# design.net
KiCad netlist of a schematic drawn in Altium Designer
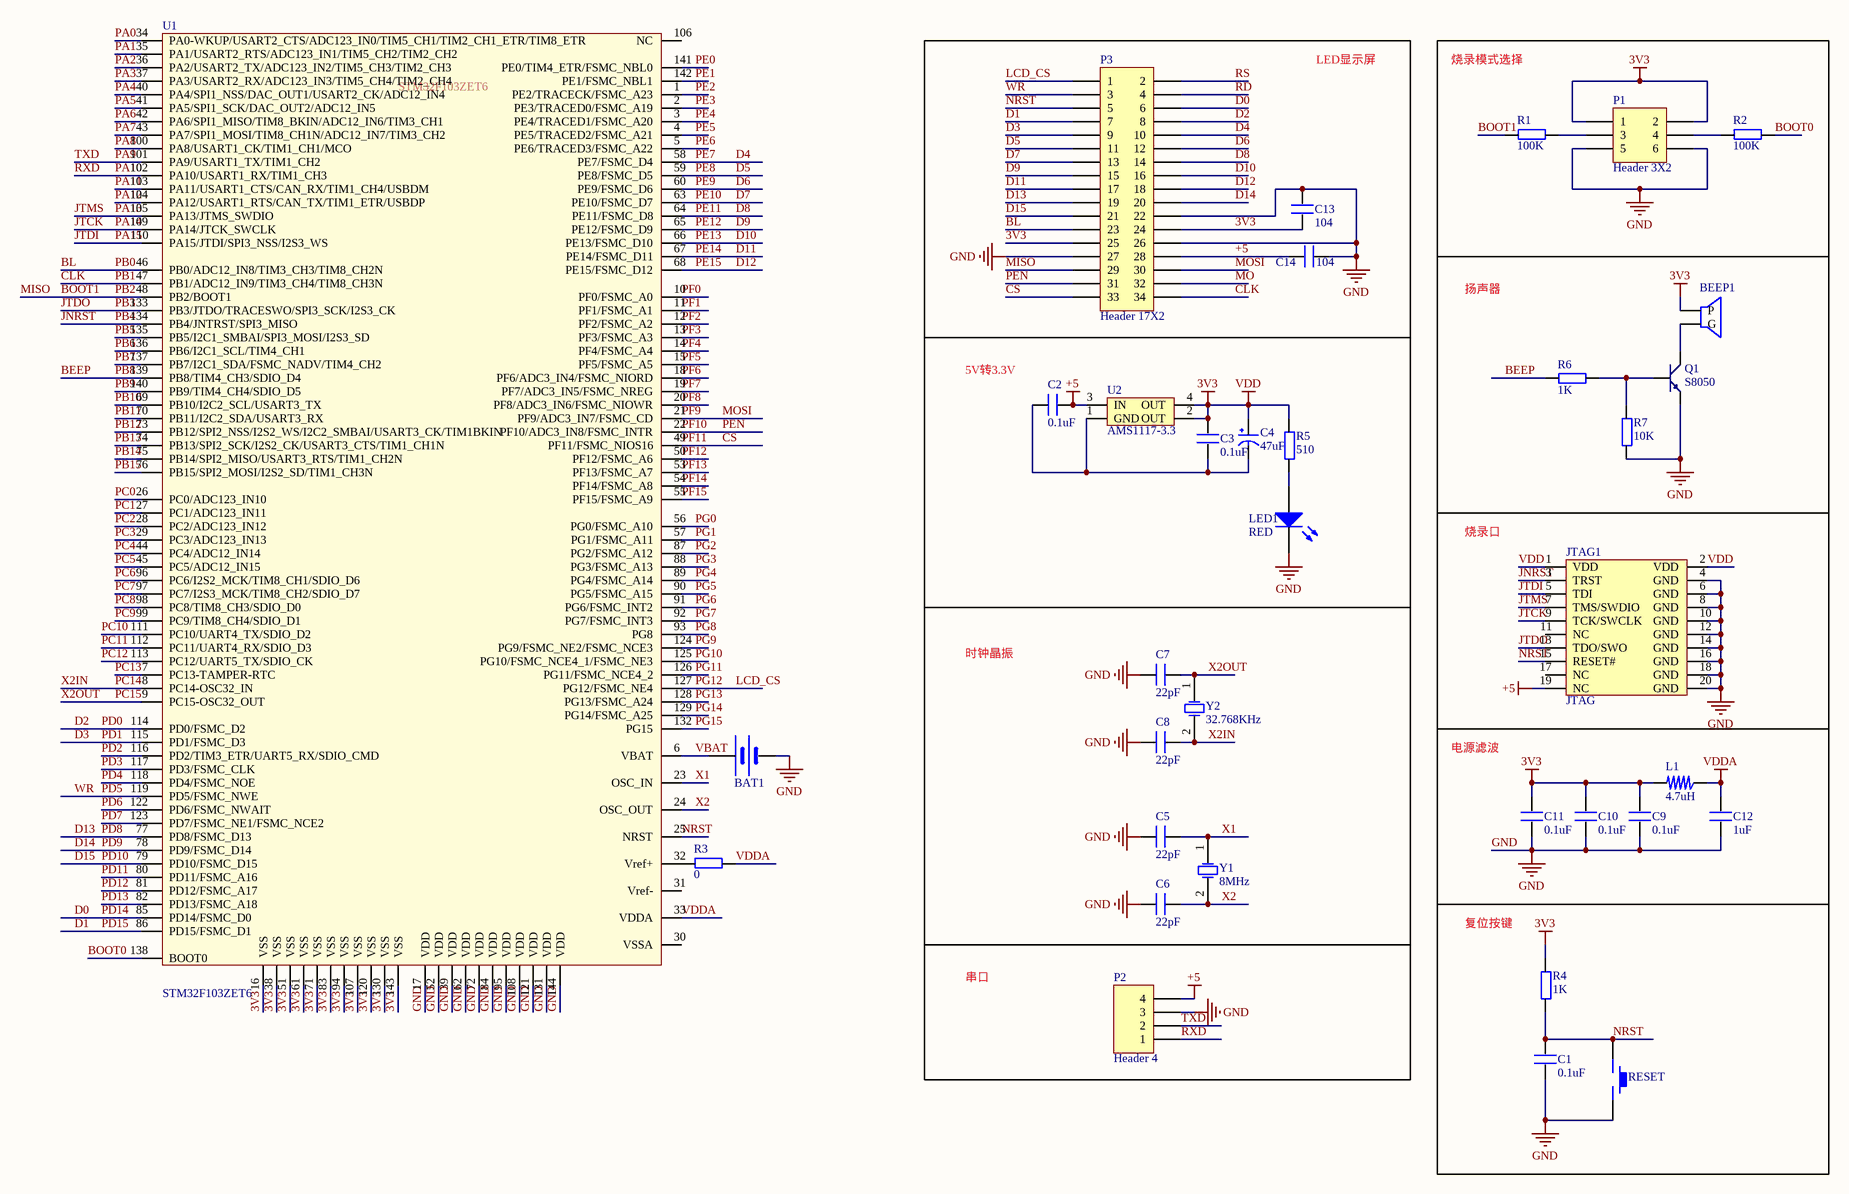
[diagram p0: 新苗.SchDoc]

(export (version "E")
  (design (tool "Eeschema 10.0.6"))
  (components
    (comp (ref "BAT1")
      (value "BATT")
      (footprint "BATM")
      (libsource (lib "WarShip V3 STM32103封装库") (part "BAT"))
    )
    (comp (ref "BEEP1")
      (value "BEEP")
      (footprint "BELL-5")
      (libsource (lib "WarShip V3 STM32103封装库") (part "BEEP"))
    )
    (comp (ref "C1")
      (value "0.1uF")
      (footprint "0603P")
      (libsource (lib "WarShip V3 STM32103封装库") (part "C"))
    )
    (comp (ref "C2")
      (value "0.1uF")
      (footprint "0603P")
      (libsource (lib "WarShip V3 STM32103封装库") (part "C"))
    )
    (comp (ref "C3")
      (value "0.1uF")
      (footprint "0603P")
      (libsource (lib "WarShip V3 STM32103封装库") (part "C"))
    )
    (comp (ref "C4")
      (value "47uF")
      (footprint "CC6.56.5")
      (libsource (lib "WarShip V3 STM32103封装库") (part "CAP"))
    )
    (comp (ref "C5") (value "22pF") (footprint "0603P") (libsource (lib "WarShip V3 STM32103封装库") (part "C")))
    (comp (ref "C6") (value "22pF") (footprint "0603P") (libsource (lib "WarShip V3 STM32103封装库") (part "C")))
    (comp (ref "C7") (value "22pF") (footprint "0603P") (libsource (lib "WarShip V3 STM32103封装库") (part "C")))
    (comp (ref "C8") (value "22pF") (footprint "0603P") (libsource (lib "WarShip V3 STM32103封装库") (part "C")))
    (comp (ref "C9")
      (value "0.1uF")
      (footprint "0603P")
      (libsource (lib "WarShip V3 STM32103封装库") (part "C"))
    )
    (comp (ref "C10")
      (value "0.1uF")
      (footprint "0603P")
      (libsource (lib "WarShip V3 STM32103封装库") (part "C"))
    )
    (comp (ref "C11")
      (value "0.1uF")
      (footprint "0603P")
      (libsource (lib "WarShip V3 STM32103封装库") (part "C"))
    )
    (comp (ref "C12") (value "1uF") (footprint "0603P") (libsource (lib "WarShip V3 STM32103封装库") (part "C")))
    (comp (ref "C13") (value "104") (footprint "0603P") (libsource (lib "WarShip V3 STM32103封装库") (part "C")))
    (comp (ref "C14") (value "104") (footprint "0603P") (libsource (lib "WarShip V3 STM32103封装库") (part "C")))
    (comp (ref "JTAG1")
      (value "JTAG")
      (footprint "JTAG_20")
      (libsource (lib "WarShip V3 STM32103封装库") (part "JTAG"))
    )
    (comp (ref "L1")
      (value "4.7uH")
      (footprint "L_SOP74")
      (libsource (lib "WarShip V3 STM32103封装库") (part "L_SOP"))
    )
    (comp (ref "LED1")
      (value "RED")
      (footprint "SMDLED")
      (description "Typical RED, GREEN, YELLOW, AMBER GaAs LED")
      (fields (field (name "PUBLISHER") "Altium Limited"))
      (libsource (lib "WarShip V3 STM32103封装库") (part "LED2"))
    )
    (comp (ref "P1")
      (value "Header 3X2")
      (footprint "HDR2X3")
      (description "Header, 3-Pin, Dual row")
      (fields (field (name "PUBLISHER") "Altium Limited"))
      (libsource (lib "Miscellaneous Connectors") (part "Header 3X2"))
    )
    (comp (ref "P2")
      (value "Header 4")
      (footprint "HDR1X4")
      (description "Header, 4-Pin")
      (fields (field (name "PUBLISHER") "Altium Limited"))
      (libsource (lib "WarShip V3 STM32103封装库") (part "Header 4"))
    )
    (comp (ref "P3")
      (value "Header 17X2")
      (footprint "HDR2X17")
      (description "Header, 17-Pin, Dual row")
      (fields (field (name "PUBLISHER") "Altium Limited"))
      (libsource (lib "Miscellaneous Connectors") (part "Header 17X2"))
    )
    (comp (ref "Q1")
      (value "S8050")
      (footprint "SOT-23R")
      (description "8050/BCW846/BCW847")
      (libsource (lib "WarShip V3 STM32103封装库") (part "NPN"))
    )
    (comp (ref "R1") (value "100K") (footprint "0603P") (libsource (lib "WarShip V3 STM32103封装库") (part "R")))
    (comp (ref "R2") (value "100K") (footprint "0603P") (libsource (lib "WarShip V3 STM32103封装库") (part "R")))
    (comp (ref "R3") (value "0") (footprint "0603P") (libsource (lib "WarShip V3 STM32103封装库") (part "R")))
    (comp (ref "R4") (value "1K") (footprint "0603P") (libsource (lib "WarShip V3 STM32103封装库") (part "R")))
    (comp (ref "R5") (value "510") (footprint "0603P") (libsource (lib "WarShip V3 STM32103封装库") (part "R")))
    (comp (ref "R6") (value "1K") (footprint "0603P") (libsource (lib "WarShip V3 STM32103封装库") (part "R")))
    (comp (ref "R7") (value "10K") (footprint "0603P") (libsource (lib "WarShip V3 STM32103封装库") (part "R")))
    (comp (ref "RESET")
      (value "KEY_M")
      (footprint "KEY_M")
      (libsource (lib "WarShip V3 STM32103封装库") (part "KEY_M"))
    )
    (comp (ref "U1")
      (value "STM32F103ZET6")
      (footprint "LQFP144")
      (libsource (lib "WarShip V3 STM32103封装库") (part "STM32F103ZET6"))
    )
    (comp (ref "U2")
      (value "AMS1117-3.3")
      (footprint "AMS1117")
      (libsource (lib "WarShip V3 STM32103封装库") (part "AMS1117"))
    )
    (comp (ref "Y1")
      (value "8MHz")
      (footprint "XTAL_US")
      (description "Crystal Oscillator")
      (fields (field (name "PUBLISHER") "Altium Limited"))
      (libsource (lib "WarShip V3 STM32103封装库") (part "XTAL"))
    )
    (comp (ref "Y2")
      (value "32.768KHz")
      (footprint "XTAL_US")
      (description "Crystal Oscillator")
      (fields (field (name "PUBLISHER") "Altium Limited"))
      (libsource (lib "WarShip V3 STM32103封装库") (part "XTAL"))
    )
  )
  (nets
    (net (code "1") (name "+5") (class "Default")
      (node (ref "C14") (pin "2") (pintype "passive"))
      (node (ref "C2") (pin "1") (pintype "passive"))
      (node (ref "JTAG1") (pin "19") (pinfunction "NC_19") (pintype "passive"))
      (node (ref "P2") (pin "4") (pinfunction "4_4") (pintype "passive"))
      (node (ref "P3") (pin "28") (pinfunction "28_28") (pintype "passive"))
      (node (ref "U2") (pin "3") (pinfunction "IN_3") (pintype "passive"))
    )
    (net (code "2") (name "/BEEP") (class "Default")
      (node (ref "R6") (pin "1") (pintype "passive"))
      (node (ref "U1") (pin "139") (pinfunction "PB8/TIM4_CH3/SDIO_D4_139") (pintype "passive"))
    )
    (net (code "3") (name "/BL") (class "Default")
      (node (ref "P3") (pin "23") (pinfunction "23_23") (pintype "passive"))
      (node (ref "U1") (pin "46") (pinfunction "PB0/ADC12_IN8/TIM3_CH3/TIM8_CH2N_46") (pintype "passive"))
    )
    (net (code "4") (name "/BOOT0") (class "Default")
      (node (ref "R2") (pin "1") (pintype "passive"))
      (node (ref "U1") (pin "138") (pinfunction "BOOT0_138") (pintype "passive"))
    )
    (net (code "5") (name "/BOOT1") (class "Default")
      (node (ref "P3") (pin "29") (pinfunction "29_29") (pintype "passive"))
      (node (ref "R1") (pin "2") (pintype "passive"))
      (node (ref "U1") (pin "48") (pinfunction "PB2/BOOT1_48") (pintype "passive"))
    )
    (net (code "6") (name "/CLK") (class "Default")
      (node (ref "P3") (pin "34") (pinfunction "34_34") (pintype "passive"))
      (node (ref "U1") (pin "47") (pinfunction "PB1/ADC12_IN9/TIM3_CH4/TIM8_CH3N_47") (pintype "passive"))
    )
    (net (code "7") (name "/CS") (class "Default")
      (node (ref "P3") (pin "33") (pinfunction "33_33") (pintype "passive"))
      (node (ref "U1") (pin "49") (pinfunction "PF11/FSMC_NIOS16_49") (pintype "passive"))
    )
    (net (code "8") (name "/D0") (class "Default")
      (node (ref "P3") (pin "6") (pinfunction "6_6") (pintype "passive"))
      (node (ref "U1") (pin "85") (pinfunction "PD14/FSMC_D0_85") (pintype "passive"))
    )
    (net (code "9") (name "/D1") (class "Default")
      (node (ref "P3") (pin "7") (pinfunction "7_7") (pintype "passive"))
      (node (ref "U1") (pin "86") (pinfunction "PD15/FSMC_D1_86") (pintype "passive"))
    )
    (net (code "10") (name "/D2") (class "Default")
      (node (ref "P3") (pin "8") (pinfunction "8_8") (pintype "passive"))
      (node (ref "U1") (pin "114") (pinfunction "PD0/FSMC_D2_114") (pintype "passive"))
    )
    (net (code "11") (name "/D3") (class "Default")
      (node (ref "P3") (pin "9") (pinfunction "9_9") (pintype "passive"))
      (node (ref "U1") (pin "115") (pinfunction "PD1/FSMC_D3_115") (pintype "passive"))
    )
    (net (code "12") (name "/D4") (class "Default")
      (node (ref "P3") (pin "10") (pinfunction "10_10") (pintype "passive"))
      (node (ref "U1") (pin "58") (pinfunction "PE7/FSMC_D4_58") (pintype "passive"))
    )
    (net (code "13") (name "/D5") (class "Default")
      (node (ref "P3") (pin "11") (pinfunction "11_11") (pintype "passive"))
      (node (ref "U1") (pin "59") (pinfunction "PE8/FSMC_D5_59") (pintype "passive"))
    )
    (net (code "14") (name "/D6") (class "Default")
      (node (ref "P3") (pin "12") (pinfunction "12_12") (pintype "passive"))
      (node (ref "U1") (pin "60") (pinfunction "PE9/FSMC_D6_60") (pintype "passive"))
    )
    (net (code "15") (name "/D7") (class "Default")
      (node (ref "P3") (pin "13") (pinfunction "13_13") (pintype "passive"))
      (node (ref "U1") (pin "63") (pinfunction "PE10/FSMC_D7_63") (pintype "passive"))
    )
    (net (code "16") (name "/D8") (class "Default")
      (node (ref "P3") (pin "14") (pinfunction "14_14") (pintype "passive"))
      (node (ref "U1") (pin "64") (pinfunction "PE11/FSMC_D8_64") (pintype "passive"))
    )
    (net (code "17") (name "/D9") (class "Default")
      (node (ref "P3") (pin "15") (pinfunction "15_15") (pintype "passive"))
      (node (ref "U1") (pin "65") (pinfunction "PE12/FSMC_D9_65") (pintype "passive"))
    )
    (net (code "18") (name "/D10") (class "Default")
      (node (ref "P3") (pin "16") (pinfunction "16_16") (pintype "passive"))
      (node (ref "U1") (pin "66") (pinfunction "PE13/FSMC_D10_66") (pintype "passive"))
    )
    (net (code "19") (name "/D11") (class "Default")
      (node (ref "P3") (pin "17") (pinfunction "17_17") (pintype "passive"))
      (node (ref "U1") (pin "67") (pinfunction "PE14/FSMC_D11_67") (pintype "passive"))
    )
    (net (code "20") (name "/D12") (class "Default")
      (node (ref "P3") (pin "18") (pinfunction "18_18") (pintype "passive"))
      (node (ref "U1") (pin "68") (pinfunction "PE15/FSMC_D12_68") (pintype "passive"))
    )
    (net (code "21") (name "/D13") (class "Default")
      (node (ref "P3") (pin "19") (pinfunction "19_19") (pintype "passive"))
      (node (ref "U1") (pin "77") (pinfunction "PD8/FSMC_D13_77") (pintype "passive"))
    )
    (net (code "22") (name "/D14") (class "Default")
      (node (ref "P3") (pin "20") (pinfunction "20_20") (pintype "passive"))
      (node (ref "U1") (pin "78") (pinfunction "PD9/FSMC_D14_78") (pintype "passive"))
    )
    (net (code "23") (name "/D15") (class "Default")
      (node (ref "P3") (pin "21") (pinfunction "21_21") (pintype "passive"))
      (node (ref "U1") (pin "79") (pinfunction "PD10/FSMC_D15_79") (pintype "passive"))
    )
    (net (code "24") (name "/JNRST") (class "Default")
      (node (ref "JTAG1") (pin "3") (pinfunction "TRST_3") (pintype "passive"))
      (node (ref "U1") (pin "134") (pinfunction "PB4/JNTRST/SPI3_MISO_134") (pintype "passive"))
    )
    (net (code "25") (name "/JTCK") (class "Default")
      (node (ref "JTAG1") (pin "9") (pinfunction "TCK/SWCLK_9") (pintype "passive"))
      (node (ref "U1") (pin "109") (pinfunction "PA14/JTCK_SWCLK_109") (pintype "passive"))
    )
    (net (code "26") (name "/JTDI") (class "Default")
      (node (ref "JTAG1") (pin "5") (pinfunction "TDI_5") (pintype "passive"))
      (node (ref "U1") (pin "110") (pinfunction "PA15/JTDI/SPI3_NSS/I2S3_WS_110") (pintype "passive"))
    )
    (net (code "27") (name "/JTDO") (class "Default")
      (node (ref "JTAG1") (pin "13") (pinfunction "TDO/SWO_13") (pintype "passive"))
      (node (ref "U1") (pin "133") (pinfunction "PB3/JTDO/TRACESWO/SPI3_SCK/I2S3_CK_133") (pintype "passive"))
    )
    (net (code "28") (name "/JTMS") (class "Default")
      (node (ref "JTAG1") (pin "7") (pinfunction "TMS/SWDIO_7") (pintype "passive"))
      (node (ref "U1") (pin "105") (pinfunction "PA13/JTMS_SWDIO_105") (pintype "passive"))
    )
    (net (code "29") (name "/LCD_CS") (class "Default")
      (node (ref "P3") (pin "1") (pinfunction "1_1") (pintype "passive"))
      (node (ref "U1") (pin "127") (pinfunction "PG12/FSMC_NE4_127") (pintype "passive"))
    )
    (net (code "30") (name "/MO") (class "Default")
      (node (ref "P3") (pin "32") (pinfunction "32_32") (pintype "passive"))
    )
    (net (code "31") (name "/MOSI") (class "Default")
      (node (ref "P3") (pin "30") (pinfunction "30_30") (pintype "passive"))
      (node (ref "U1") (pin "21") (pinfunction "PF9/ADC3_IN7/FSMC_CD_21") (pintype "passive"))
    )
    (net (code "32") (name "/NRST") (class "Default")
      (node (ref "C1") (pin "2") (pintype "passive"))
      (node (ref "JTAG1") (pin "15") (pinfunction "RESET#_15") (pintype "passive"))
      (node (ref "P3") (pin "5") (pinfunction "5_5") (pintype "passive"))
      (node (ref "R4") (pin "1") (pintype "passive"))
      (node (ref "RESET") (pin "1") (pinfunction "1_1") (pintype "passive"))
      (node (ref "U1") (pin "25") (pinfunction "NRST_25") (pintype "passive"))
    )
    (net (code "33") (name "/PA0") (class "Default")
      (node (ref "U1") (pin "34") (pinfunction "PA0-WKUP/USART2_CTS/ADC123_IN0/TIM5_CH1/TIM2_CH1_ETR/TIM8_ETR_34") (pintype "passive"))
    )
    (net (code "34") (name "/PA1") (class "Default")
      (node (ref "U1") (pin "35") (pinfunction "PA1/USART2_RTS/ADC123_IN1/TIM5_CH2/TIM2_CH2_35") (pintype "passive"))
    )
    (net (code "35") (name "/PA2") (class "Default")
      (node (ref "U1") (pin "36") (pinfunction "PA2/USART2_TX/ADC123_IN2/TIM5_CH3/TIM2_CH3_36") (pintype "passive"))
    )
    (net (code "36") (name "/PA3") (class "Default")
      (node (ref "U1") (pin "37") (pinfunction "PA3/USART2_RX/ADC123_IN3/TIM5_CH4/TIM2_CH4_37") (pintype "passive"))
    )
    (net (code "37") (name "/PA4") (class "Default")
      (node (ref "U1") (pin "40") (pinfunction "PA4/SPI1_NSS/DAC_OUT1/USART2_CK/ADC12_IN4_40") (pintype "passive"))
    )
    (net (code "38") (name "/PA5") (class "Default")
      (node (ref "U1") (pin "41") (pinfunction "PA5/SPI1_SCK/DAC_OUT2/ADC12_IN5_41") (pintype "passive"))
    )
    (net (code "39") (name "/PA6") (class "Default")
      (node (ref "U1") (pin "42") (pinfunction "PA6/SPI1_MISO/TIM8_BKIN/ADC12_IN6/TIM3_CH1_42") (pintype "passive"))
    )
    (net (code "40") (name "/PA7") (class "Default")
      (node (ref "U1") (pin "43") (pinfunction "PA7/SPI1_MOSI/TIM8_CH1N/ADC12_IN7/TIM3_CH2_43") (pintype "passive"))
    )
    (net (code "41") (name "/PA8") (class "Default")
      (node (ref "U1") (pin "100") (pinfunction "PA8/USART1_CK/TIM1_CH1/MCO_100") (pintype "passive"))
    )
    (net (code "42") (name "/PA9") (class "Default")
      (node (ref "P2") (pin "2") (pinfunction "2_2") (pintype "passive"))
      (node (ref "U1") (pin "101") (pinfunction "PA9/USART1_TX/TIM1_CH2_101") (pintype "passive"))
    )
    (net (code "43") (name "/PA10") (class "Default")
      (node (ref "P2") (pin "1") (pinfunction "1_1") (pintype "passive"))
      (node (ref "U1") (pin "102") (pinfunction "PA10/USART1_RX/TIM1_CH3_102") (pintype "passive"))
    )
    (net (code "44") (name "/PA11") (class "Default")
      (node (ref "U1") (pin "103") (pinfunction "PA11/USART1_CTS/CAN_RX/TIM1_CH4/USBDM_103") (pintype "passive"))
    )
    (net (code "45") (name "/PA12") (class "Default")
      (node (ref "U1") (pin "104") (pinfunction "PA12/USART1_RTS/CAN_TX/TIM1_ETR/USBDP_104") (pintype "passive"))
    )
    (net (code "46") (name "/PB5") (class "Default")
      (node (ref "U1") (pin "135") (pinfunction "PB5/I2C1_SMBAI/SPI3_MOSI/I2S3_SD_135") (pintype "passive"))
    )
    (net (code "47") (name "/PB6") (class "Default")
      (node (ref "U1") (pin "136") (pinfunction "PB6/I2C1_SCL/TIM4_CH1_136") (pintype "passive"))
    )
    (net (code "48") (name "/PB7") (class "Default")
      (node (ref "U1") (pin "137") (pinfunction "PB7/I2C1_SDA/FSMC_NADV/TIM4_CH2_137") (pintype "passive"))
    )
    (net (code "49") (name "/PB9") (class "Default")
      (node (ref "U1") (pin "140") (pinfunction "PB9/TIM4_CH4/SDIO_D5_140") (pintype "passive"))
    )
    (net (code "50") (name "/PB10") (class "Default")
      (node (ref "U1") (pin "69") (pinfunction "PB10/I2C2_SCL/USART3_TX_69") (pintype "passive"))
    )
    (net (code "51") (name "/PB11") (class "Default")
      (node (ref "U1") (pin "70") (pinfunction "PB11/I2C2_SDA/USART3_RX_70") (pintype "passive"))
    )
    (net (code "52") (name "/PB12") (class "Default")
      (node (ref "U1") (pin "73") (pinfunction "PB12/SPI2_NSS/I2S2_WS/I2C2_SMBAI/USART3_CK/TIM1BKIN_73") (pintype "passive"))
    )
    (net (code "53") (name "/PB13") (class "Default")
      (node (ref "U1") (pin "74") (pinfunction "PB13/SPI2_SCK/I2S2_CK/USART3_CTS/TIM1_CH1N_74") (pintype "passive"))
    )
    (net (code "54") (name "/PB14") (class "Default")
      (node (ref "U1") (pin "75") (pinfunction "PB14/SPI2_MISO/USART3_RTS/TIM1_CH2N_75") (pintype "passive"))
    )
    (net (code "55") (name "/PB15") (class "Default")
      (node (ref "U1") (pin "76") (pinfunction "PB15/SPI2_MOSI/I2S2_SD/TIM1_CH3N_76") (pintype "passive"))
    )
    (net (code "56") (name "/PC0") (class "Default")
      (node (ref "U1") (pin "26") (pinfunction "PC0/ADC123_IN10_26") (pintype "passive"))
    )
    (net (code "57") (name "/PC1") (class "Default")
      (node (ref "U1") (pin "27") (pinfunction "PC1/ADC123_IN11_27") (pintype "passive"))
    )
    (net (code "58") (name "/PC2") (class "Default")
      (node (ref "U1") (pin "28") (pinfunction "PC2/ADC123_IN12_28") (pintype "passive"))
    )
    (net (code "59") (name "/PC3") (class "Default")
      (node (ref "U1") (pin "29") (pinfunction "PC3/ADC123_IN13_29") (pintype "passive"))
    )
    (net (code "60") (name "/PC4") (class "Default")
      (node (ref "U1") (pin "44") (pinfunction "PC4/ADC12_IN14_44") (pintype "passive"))
    )
    (net (code "61") (name "/PC5") (class "Default")
      (node (ref "U1") (pin "45") (pinfunction "PC5/ADC12_IN15_45") (pintype "passive"))
    )
    (net (code "62") (name "/PC6") (class "Default")
      (node (ref "U1") (pin "96") (pinfunction "PC6/I2S2_MCK/TIM8_CH1/SDIO_D6_96") (pintype "passive"))
    )
    (net (code "63") (name "/PC7") (class "Default")
      (node (ref "U1") (pin "97") (pinfunction "PC7/I2S3_MCK/TIM8_CH2/SDIO_D7_97") (pintype "passive"))
    )
    (net (code "64") (name "/PC8") (class "Default")
      (node (ref "U1") (pin "98") (pinfunction "PC8/TIM8_CH3/SDIO_D0_98") (pintype "passive"))
    )
    (net (code "65") (name "/PC9") (class "Default")
      (node (ref "U1") (pin "99") (pinfunction "PC9/TIM8_CH4/SDIO_D1_99") (pintype "passive"))
    )
    (net (code "66") (name "/PC10") (class "Default")
      (node (ref "U1") (pin "111") (pinfunction "PC10/UART4_TX/SDIO_D2_111") (pintype "passive"))
    )
    (net (code "67") (name "/PC11") (class "Default")
      (node (ref "U1") (pin "112") (pinfunction "PC11/UART4_RX/SDIO_D3_112") (pintype "passive"))
    )
    (net (code "68") (name "/PC12") (class "Default")
      (node (ref "U1") (pin "113") (pinfunction "PC12/UART5_TX/SDIO_CK_113") (pintype "passive"))
    )
    (net (code "69") (name "/PC13") (class "Default")
      (node (ref "U1") (pin "7") (pinfunction "PC13-TAMPER-RTC_7") (pintype "passive"))
    )
    (net (code "70") (name "/PC14") (class "Default")
      (node (ref "C8") (pin "2") (pintype "passive"))
      (node (ref "U1") (pin "8") (pinfunction "PC14-OSC32_IN_8") (pintype "passive"))
      (node (ref "Y2") (pin "2") (pinfunction "OSC2_2") (pintype "passive"))
    )
    (net (code "71") (name "/PC15") (class "Default")
      (node (ref "C7") (pin "2") (pintype "passive"))
      (node (ref "U1") (pin "9") (pinfunction "PC15-OSC32_OUT_9") (pintype "passive"))
      (node (ref "Y2") (pin "1") (pinfunction "OSC1_1") (pintype "passive"))
    )
    (net (code "72") (name "/PD2") (class "Default")
      (node (ref "U1") (pin "116") (pinfunction "PD2/TIM3_ETR/UART5_RX/SDIO_CMD_116") (pintype "passive"))
    )
    (net (code "73") (name "/PD3") (class "Default")
      (node (ref "U1") (pin "117") (pinfunction "PD3/FSMC_CLK_117") (pintype "passive"))
    )
    (net (code "74") (name "/PD4") (class "Default")
      (node (ref "U1") (pin "118") (pinfunction "PD4/FSMC_NOE_118") (pintype "passive"))
    )
    (net (code "75") (name "/PD5") (class "Default")
      (node (ref "P3") (pin "3") (pinfunction "3_3") (pintype "passive"))
      (node (ref "U1") (pin "119") (pinfunction "PD5/FSMC_NWE_119") (pintype "passive"))
    )
    (net (code "76") (name "/PD6") (class "Default")
      (node (ref "U1") (pin "122") (pinfunction "PD6/FSMC_NWAIT_122") (pintype "passive"))
    )
    (net (code "77") (name "/PD7") (class "Default")
      (node (ref "U1") (pin "123") (pinfunction "PD7/FSMC_NE1/FSMC_NCE2_123") (pintype "passive"))
    )
    (net (code "78") (name "/PD11") (class "Default")
      (node (ref "U1") (pin "80") (pinfunction "PD11/FSMC_A16_80") (pintype "passive"))
    )
    (net (code "79") (name "/PD12") (class "Default")
      (node (ref "U1") (pin "81") (pinfunction "PD12/FSMC_A17_81") (pintype "passive"))
    )
    (net (code "80") (name "/PD13") (class "Default")
      (node (ref "U1") (pin "82") (pinfunction "PD13/FSMC_A18_82") (pintype "passive"))
    )
    (net (code "81") (name "/PE0") (class "Default")
      (node (ref "U1") (pin "141") (pinfunction "PE0/TIM4_ETR/FSMC_NBL0_141") (pintype "passive"))
    )
    (net (code "82") (name "/PE1") (class "Default")
      (node (ref "U1") (pin "142") (pinfunction "PE1/FSMC_NBL1_142") (pintype "passive"))
    )
    (net (code "83") (name "/PE2") (class "Default")
      (node (ref "U1") (pin "1") (pinfunction "PE2/TRACECK/FSMC_A23_1") (pintype "passive"))
    )
    (net (code "84") (name "/PE3") (class "Default")
      (node (ref "U1") (pin "2") (pinfunction "PE3/TRACED0/FSMC_A19_2") (pintype "passive"))
    )
    (net (code "85") (name "/PE4") (class "Default")
      (node (ref "U1") (pin "3") (pinfunction "PE4/TRACED1/FSMC_A20_3") (pintype "passive"))
    )
    (net (code "86") (name "/PE5") (class "Default")
      (node (ref "U1") (pin "4") (pinfunction "PE5/TRACED2/FSMC_A21_4") (pintype "passive"))
    )
    (net (code "87") (name "/PE6") (class "Default")
      (node (ref "U1") (pin "5") (pinfunction "PE6/TRACED3/FSMC_A22_5") (pintype "passive"))
    )
    (net (code "88") (name "/PEN") (class "Default")
      (node (ref "P3") (pin "31") (pinfunction "31_31") (pintype "passive"))
      (node (ref "U1") (pin "22") (pinfunction "PF10/ADC3_IN8/FSMC_INTR_22") (pintype "passive"))
    )
    (net (code "89") (name "/PF0") (class "Default")
      (node (ref "U1") (pin "10") (pinfunction "PF0/FSMC_A0_10") (pintype "passive"))
    )
    (net (code "90") (name "/PF1") (class "Default")
      (node (ref "U1") (pin "11") (pinfunction "PF1/FSMC_A1_11") (pintype "passive"))
    )
    (net (code "91") (name "/PF2") (class "Default")
      (node (ref "U1") (pin "12") (pinfunction "PF2/FSMC_A2_12") (pintype "passive"))
    )
    (net (code "92") (name "/PF3") (class "Default")
      (node (ref "U1") (pin "13") (pinfunction "PF3/FSMC_A3_13") (pintype "passive"))
    )
    (net (code "93") (name "/PF4") (class "Default")
      (node (ref "U1") (pin "14") (pinfunction "PF4/FSMC_A4_14") (pintype "passive"))
    )
    (net (code "94") (name "/PF5") (class "Default")
      (node (ref "U1") (pin "15") (pinfunction "PF5/FSMC_A5_15") (pintype "passive"))
    )
    (net (code "95") (name "/PF6") (class "Default")
      (node (ref "U1") (pin "18") (pinfunction "PF6/ADC3_IN4/FSMC_NIORD_18") (pintype "passive"))
    )
    (net (code "96") (name "/PF7") (class "Default")
      (node (ref "U1") (pin "19") (pinfunction "PF7/ADC3_IN5/FSMC_NREG_19") (pintype "passive"))
    )
    (net (code "97") (name "/PF8") (class "Default")
      (node (ref "U1") (pin "20") (pinfunction "PF8/ADC3_IN6/FSMC_NIOWR_20") (pintype "passive"))
    )
    (net (code "98") (name "/PF12") (class "Default")
      (node (ref "U1") (pin "50") (pinfunction "PF12/FSMC_A6_50") (pintype "passive"))
    )
    (net (code "99") (name "/PF13") (class "Default")
      (node (ref "U1") (pin "53") (pinfunction "PF13/FSMC_A7_53") (pintype "passive"))
    )
    (net (code "100") (name "/PF14") (class "Default")
      (node (ref "U1") (pin "54") (pinfunction "PF14/FSMC_A8_54") (pintype "passive"))
    )
    (net (code "101") (name "/PF15") (class "Default")
      (node (ref "U1") (pin "55") (pinfunction "PF15/FSMC_A9_55") (pintype "passive"))
    )
    (net (code "102") (name "/PG0") (class "Default")
      (node (ref "U1") (pin "56") (pinfunction "PG0/FSMC_A10_56") (pintype "passive"))
    )
    (net (code "103") (name "/PG1") (class "Default")
      (node (ref "U1") (pin "57") (pinfunction "PG1/FSMC_A11_57") (pintype "passive"))
    )
    (net (code "104") (name "/PG2") (class "Default")
      (node (ref "U1") (pin "87") (pinfunction "PG2/FSMC_A12_87") (pintype "passive"))
    )
    (net (code "105") (name "/PG3") (class "Default")
      (node (ref "U1") (pin "88") (pinfunction "PG3/FSMC_A13_88") (pintype "passive"))
    )
    (net (code "106") (name "/PG4") (class "Default")
      (node (ref "U1") (pin "89") (pinfunction "PG4/FSMC_A14_89") (pintype "passive"))
    )
    (net (code "107") (name "/PG5") (class "Default")
      (node (ref "U1") (pin "90") (pinfunction "PG5/FSMC_A15_90") (pintype "passive"))
    )
    (net (code "108") (name "/PG6") (class "Default")
      (node (ref "U1") (pin "91") (pinfunction "PG6/FSMC_INT2_91") (pintype "passive"))
    )
    (net (code "109") (name "/PG7") (class "Default")
      (node (ref "U1") (pin "92") (pinfunction "PG7/FSMC_INT3_92") (pintype "passive"))
    )
    (net (code "110") (name "/PG8") (class "Default")
      (node (ref "U1") (pin "93") (pinfunction "PG8_93") (pintype "passive"))
    )
    (net (code "111") (name "/PG9") (class "Default")
      (node (ref "U1") (pin "124") (pinfunction "PG9/FSMC_NE2/FSMC_NCE3_124") (pintype "passive"))
    )
    (net (code "112") (name "/PG10") (class "Default")
      (node (ref "U1") (pin "125") (pinfunction "PG10/FSMC_NCE4_1/FSMC_NE3_125") (pintype "passive"))
    )
    (net (code "113") (name "/PG11") (class "Default")
      (node (ref "U1") (pin "126") (pinfunction "PG11/FSMC_NCE4_2_126") (pintype "passive"))
    )
    (net (code "114") (name "/PG13") (class "Default")
      (node (ref "U1") (pin "128") (pinfunction "PG13/FSMC_A24_128") (pintype "passive"))
    )
    (net (code "115") (name "/PG14") (class "Default")
      (node (ref "U1") (pin "129") (pinfunction "PG14/FSMC_A25_129") (pintype "passive"))
    )
    (net (code "116") (name "/PG15") (class "Default")
      (node (ref "U1") (pin "132") (pinfunction "PG15_132") (pintype "passive"))
    )
    (net (code "117") (name "/RD") (class "Default")
      (node (ref "P3") (pin "4") (pinfunction "4_4") (pintype "passive"))
    )
    (net (code "118") (name "/RS") (class "Default")
      (node (ref "P3") (pin "2") (pinfunction "2_2") (pintype "passive"))
    )
    (net (code "119") (name "/VBAT") (class "Default")
      (node (ref "BAT1") (pin "1") (pinfunction "VCC_1") (pintype "passive"))
      (node (ref "U1") (pin "6") (pinfunction "VBAT_6") (pintype "passive"))
    )
    (net (code "120") (name "/X1") (class "Default")
      (node (ref "C5") (pin "2") (pintype "passive"))
      (node (ref "U1") (pin "23") (pinfunction "OSC_IN_23") (pintype "passive"))
      (node (ref "Y1") (pin "1") (pinfunction "OSC1_1") (pintype "passive"))
    )
    (net (code "121") (name "/X2") (class "Default")
      (node (ref "C6") (pin "2") (pintype "passive"))
      (node (ref "U1") (pin "24") (pinfunction "OSC_OUT_24") (pintype "passive"))
      (node (ref "Y1") (pin "2") (pinfunction "OSC2_2") (pintype "passive"))
    )
    (net (code "122") (name "3V3") (class "Default")
      (node (ref "BEEP1") (pin "1") (pinfunction "P_1") (pintype "passive"))
      (node (ref "C10") (pin "2") (pintype "passive"))
      (node (ref "C11") (pin "2") (pintype "passive"))
      (node (ref "C13") (pin "1") (pintype "passive"))
      (node (ref "C3") (pin "2") (pintype "passive"))
      (node (ref "C4") (pin "1") (pinfunction "VCC_1") (pintype "passive"))
      (node (ref "C9") (pin "2") (pintype "passive"))
      (node (ref "JTAG1") (pin "1") (pinfunction "VDD_1") (pintype "passive"))
      (node (ref "JTAG1") (pin "2") (pinfunction "VDD_2") (pintype "passive"))
      (node (ref "L1") (pin "2") (pinfunction "2_2") (pintype "passive"))
      (node (ref "P1") (pin "1") (pinfunction "1_1") (pintype "passive"))
      (node (ref "P1") (pin "2") (pinfunction "2_2") (pintype "passive"))
      (node (ref "P3") (pin "24") (pinfunction "24_24") (pintype "passive"))
      (node (ref "P3") (pin "25") (pinfunction "25_25") (pintype "passive"))
      (node (ref "R4") (pin "2") (pintype "passive"))
      (node (ref "R5") (pin "2") (pintype "passive"))
      (node (ref "U1") (pin "107") (pinfunction "VSS_107") (pintype "passive"))
      (node (ref "U1") (pin "120") (pinfunction "VSS_120") (pintype "passive"))
      (node (ref "U1") (pin "130") (pinfunction "VSS_130") (pintype "passive"))
      (node (ref "U1") (pin "143") (pinfunction "VSS_143") (pintype "passive"))
      (node (ref "U1") (pin "16") (pinfunction "VSS_16") (pintype "passive"))
      (node (ref "U1") (pin "38") (pinfunction "VSS_38") (pintype "passive"))
      (node (ref "U1") (pin "51") (pinfunction "VSS_51") (pintype "passive"))
      (node (ref "U1") (pin "61") (pinfunction "VSS_61") (pintype "passive"))
      (node (ref "U1") (pin "71") (pinfunction "VSS_71") (pintype "passive"))
      (node (ref "U1") (pin "83") (pinfunction "VSS_83") (pintype "passive"))
      (node (ref "U1") (pin "94") (pinfunction "VSS_94") (pintype "passive"))
      (node (ref "U2") (pin "2") (pinfunction "OUT_2") (pintype "passive"))
      (node (ref "U2") (pin "4") (pinfunction "OUT_4") (pintype "passive"))
    )
    (net (code "123") (name "GND") (class "Default")
      (node (ref "BAT1") (pin "2") (pinfunction "GND_2") (pintype "passive"))
      (node (ref "C1") (pin "1") (pintype "passive"))
      (node (ref "C10") (pin "1") (pintype "passive"))
      (node (ref "C11") (pin "1") (pintype "passive"))
      (node (ref "C12") (pin "1") (pintype "passive"))
      (node (ref "C13") (pin "2") (pintype "passive"))
      (node (ref "C14") (pin "1") (pintype "passive"))
      (node (ref "C5") (pin "1") (pintype "passive"))
      (node (ref "C6") (pin "1") (pintype "passive"))
      (node (ref "C7") (pin "1") (pintype "passive"))
      (node (ref "C8") (pin "1") (pintype "passive"))
      (node (ref "C9") (pin "1") (pintype "passive"))
      (node (ref "JTAG1") (pin "10") (pinfunction "GND_10") (pintype "passive"))
      (node (ref "JTAG1") (pin "12") (pinfunction "GND_12") (pintype "passive"))
      (node (ref "JTAG1") (pin "14") (pinfunction "GND_14") (pintype "passive"))
      (node (ref "JTAG1") (pin "16") (pinfunction "GND_16") (pintype "passive"))
      (node (ref "JTAG1") (pin "18") (pinfunction "GND_18") (pintype "passive"))
      (node (ref "JTAG1") (pin "20") (pinfunction "GND_20") (pintype "passive"))
      (node (ref "JTAG1") (pin "4") (pinfunction "GND_4") (pintype "passive"))
      (node (ref "JTAG1") (pin "6") (pinfunction "GND_6") (pintype "passive"))
      (node (ref "JTAG1") (pin "8") (pinfunction "GND_8") (pintype "passive"))
      (node (ref "LED1") (pin "2") (pinfunction "K_2") (pintype "passive"))
      (node (ref "P1") (pin "5") (pinfunction "5_5") (pintype "passive"))
      (node (ref "P1") (pin "6") (pinfunction "6_6") (pintype "passive"))
      (node (ref "P2") (pin "3") (pinfunction "3_3") (pintype "passive"))
      (node (ref "P3") (pin "22") (pinfunction "22_22") (pintype "passive"))
      (node (ref "P3") (pin "26") (pinfunction "26_26") (pintype "passive"))
      (node (ref "P3") (pin "27") (pinfunction "27_27") (pintype "passive"))
      (node (ref "Q1") (pin "1") (pinfunction "E_1") (pintype "passive"))
      (node (ref "R7") (pin "1") (pintype "passive"))
      (node (ref "RESET") (pin "2") (pinfunction "2_2") (pintype "passive"))
      (node (ref "U1") (pin "108") (pinfunction "VDD_108") (pintype "passive"))
      (node (ref "U1") (pin "121") (pinfunction "VDD_121") (pintype "passive"))
      (node (ref "U1") (pin "131") (pinfunction "VDD_131") (pintype "passive"))
      (node (ref "U1") (pin "144") (pinfunction "VDD_144") (pintype "passive"))
      (node (ref "U1") (pin "17") (pinfunction "VDD_17") (pintype "passive"))
      (node (ref "U1") (pin "39") (pinfunction "VDD_39") (pintype "passive"))
      (node (ref "U1") (pin "52") (pinfunction "VDD_52") (pintype "passive"))
      (node (ref "U1") (pin "62") (pinfunction "VDD_62") (pintype "passive"))
      (node (ref "U1") (pin "72") (pinfunction "VDD_72") (pintype "passive"))
      (node (ref "U1") (pin "84") (pinfunction "VDD_84") (pintype "passive"))
      (node (ref "U1") (pin "95") (pinfunction "VDD_95") (pintype "passive"))
    )
    (net (code "124") (name "Net-(BEEP1-G)") (class "Default")
      (node (ref "BEEP1") (pin "2") (pinfunction "G_2") (pintype "passive"))
      (node (ref "Q1") (pin "3") (pinfunction "C_3") (pintype "passive"))
    )
    (net (code "125") (name "Net-(C4-GND)") (class "Default")
      (node (ref "C2") (pin "2") (pintype "passive"))
      (node (ref "C3") (pin "1") (pintype "passive"))
      (node (ref "C4") (pin "2") (pinfunction "GND_2") (pintype "passive"))
      (node (ref "U2") (pin "1") (pinfunction "GND_1") (pintype "passive"))
    )
    (net (code "126") (name "Net-(LED1-A)") (class "Default")
      (node (ref "LED1") (pin "1") (pinfunction "A_1") (pintype "passive"))
      (node (ref "R5") (pin "1") (pintype "passive"))
    )
    (net (code "127") (name "Net-(P1-Pad3)") (class "Default")
      (node (ref "P1") (pin "3") (pinfunction "3_3") (pintype "passive"))
      (node (ref "R1") (pin "1") (pintype "passive"))
    )
    (net (code "128") (name "Net-(P1-Pad4)") (class "Default")
      (node (ref "P1") (pin "4") (pinfunction "4_4") (pintype "passive"))
      (node (ref "R2") (pin "2") (pintype "passive"))
    )
    (net (code "129") (name "Net-(Q1-B)") (class "Default")
      (node (ref "Q1") (pin "2") (pinfunction "B_2") (pintype "passive"))
      (node (ref "R6") (pin "2") (pintype "passive"))
      (node (ref "R7") (pin "2") (pintype "passive"))
    )
    (net (code "130") (name "Net-(U1-Vref+)") (class "Default")
      (node (ref "R3") (pin "2") (pintype "passive"))
      (node (ref "U1") (pin "32") (pinfunction "Vref+_32") (pintype "passive"))
    )
    (net (code "131") (name "VDDA") (class "Default")
      (node (ref "C12") (pin "2") (pintype "passive"))
      (node (ref "L1") (pin "1") (pinfunction "1_1") (pintype "passive"))
      (node (ref "R3") (pin "1") (pintype "passive"))
      (node (ref "U1") (pin "33") (pinfunction "VDDA_33") (pintype "passive"))
    )
    (net (code "132") (name "unconnected-(JTAG1-NC-Pad11)") (class "Default")
      (node (ref "JTAG1") (pin "11") (pinfunction "NC_11") (pintype "passive"))
    )
    (net (code "133") (name "unconnected-(JTAG1-NC-Pad17)") (class "Default")
      (node (ref "JTAG1") (pin "17") (pinfunction "NC_17") (pintype "passive"))
    )
    (net (code "134") (name "unconnected-(U1-NC-Pad106)") (class "Default")
      (node (ref "U1") (pin "106") (pinfunction "NC_106") (pintype "passive"))
    )
    (net (code "135") (name "unconnected-(U1-VSSA-Pad30)") (class "Default")
      (node (ref "U1") (pin "30") (pinfunction "VSSA_30") (pintype "passive"))
    )
    (net (code "136") (name "unconnected-(U1-Vref--Pad31)") (class "Default")
      (node (ref "U1") (pin "31") (pinfunction "Vref-_31") (pintype "passive"))
    )
  )
)
